# Scheme_UPS_RPI.net
KiCad netlist of a schematic drawn in Altium Designer
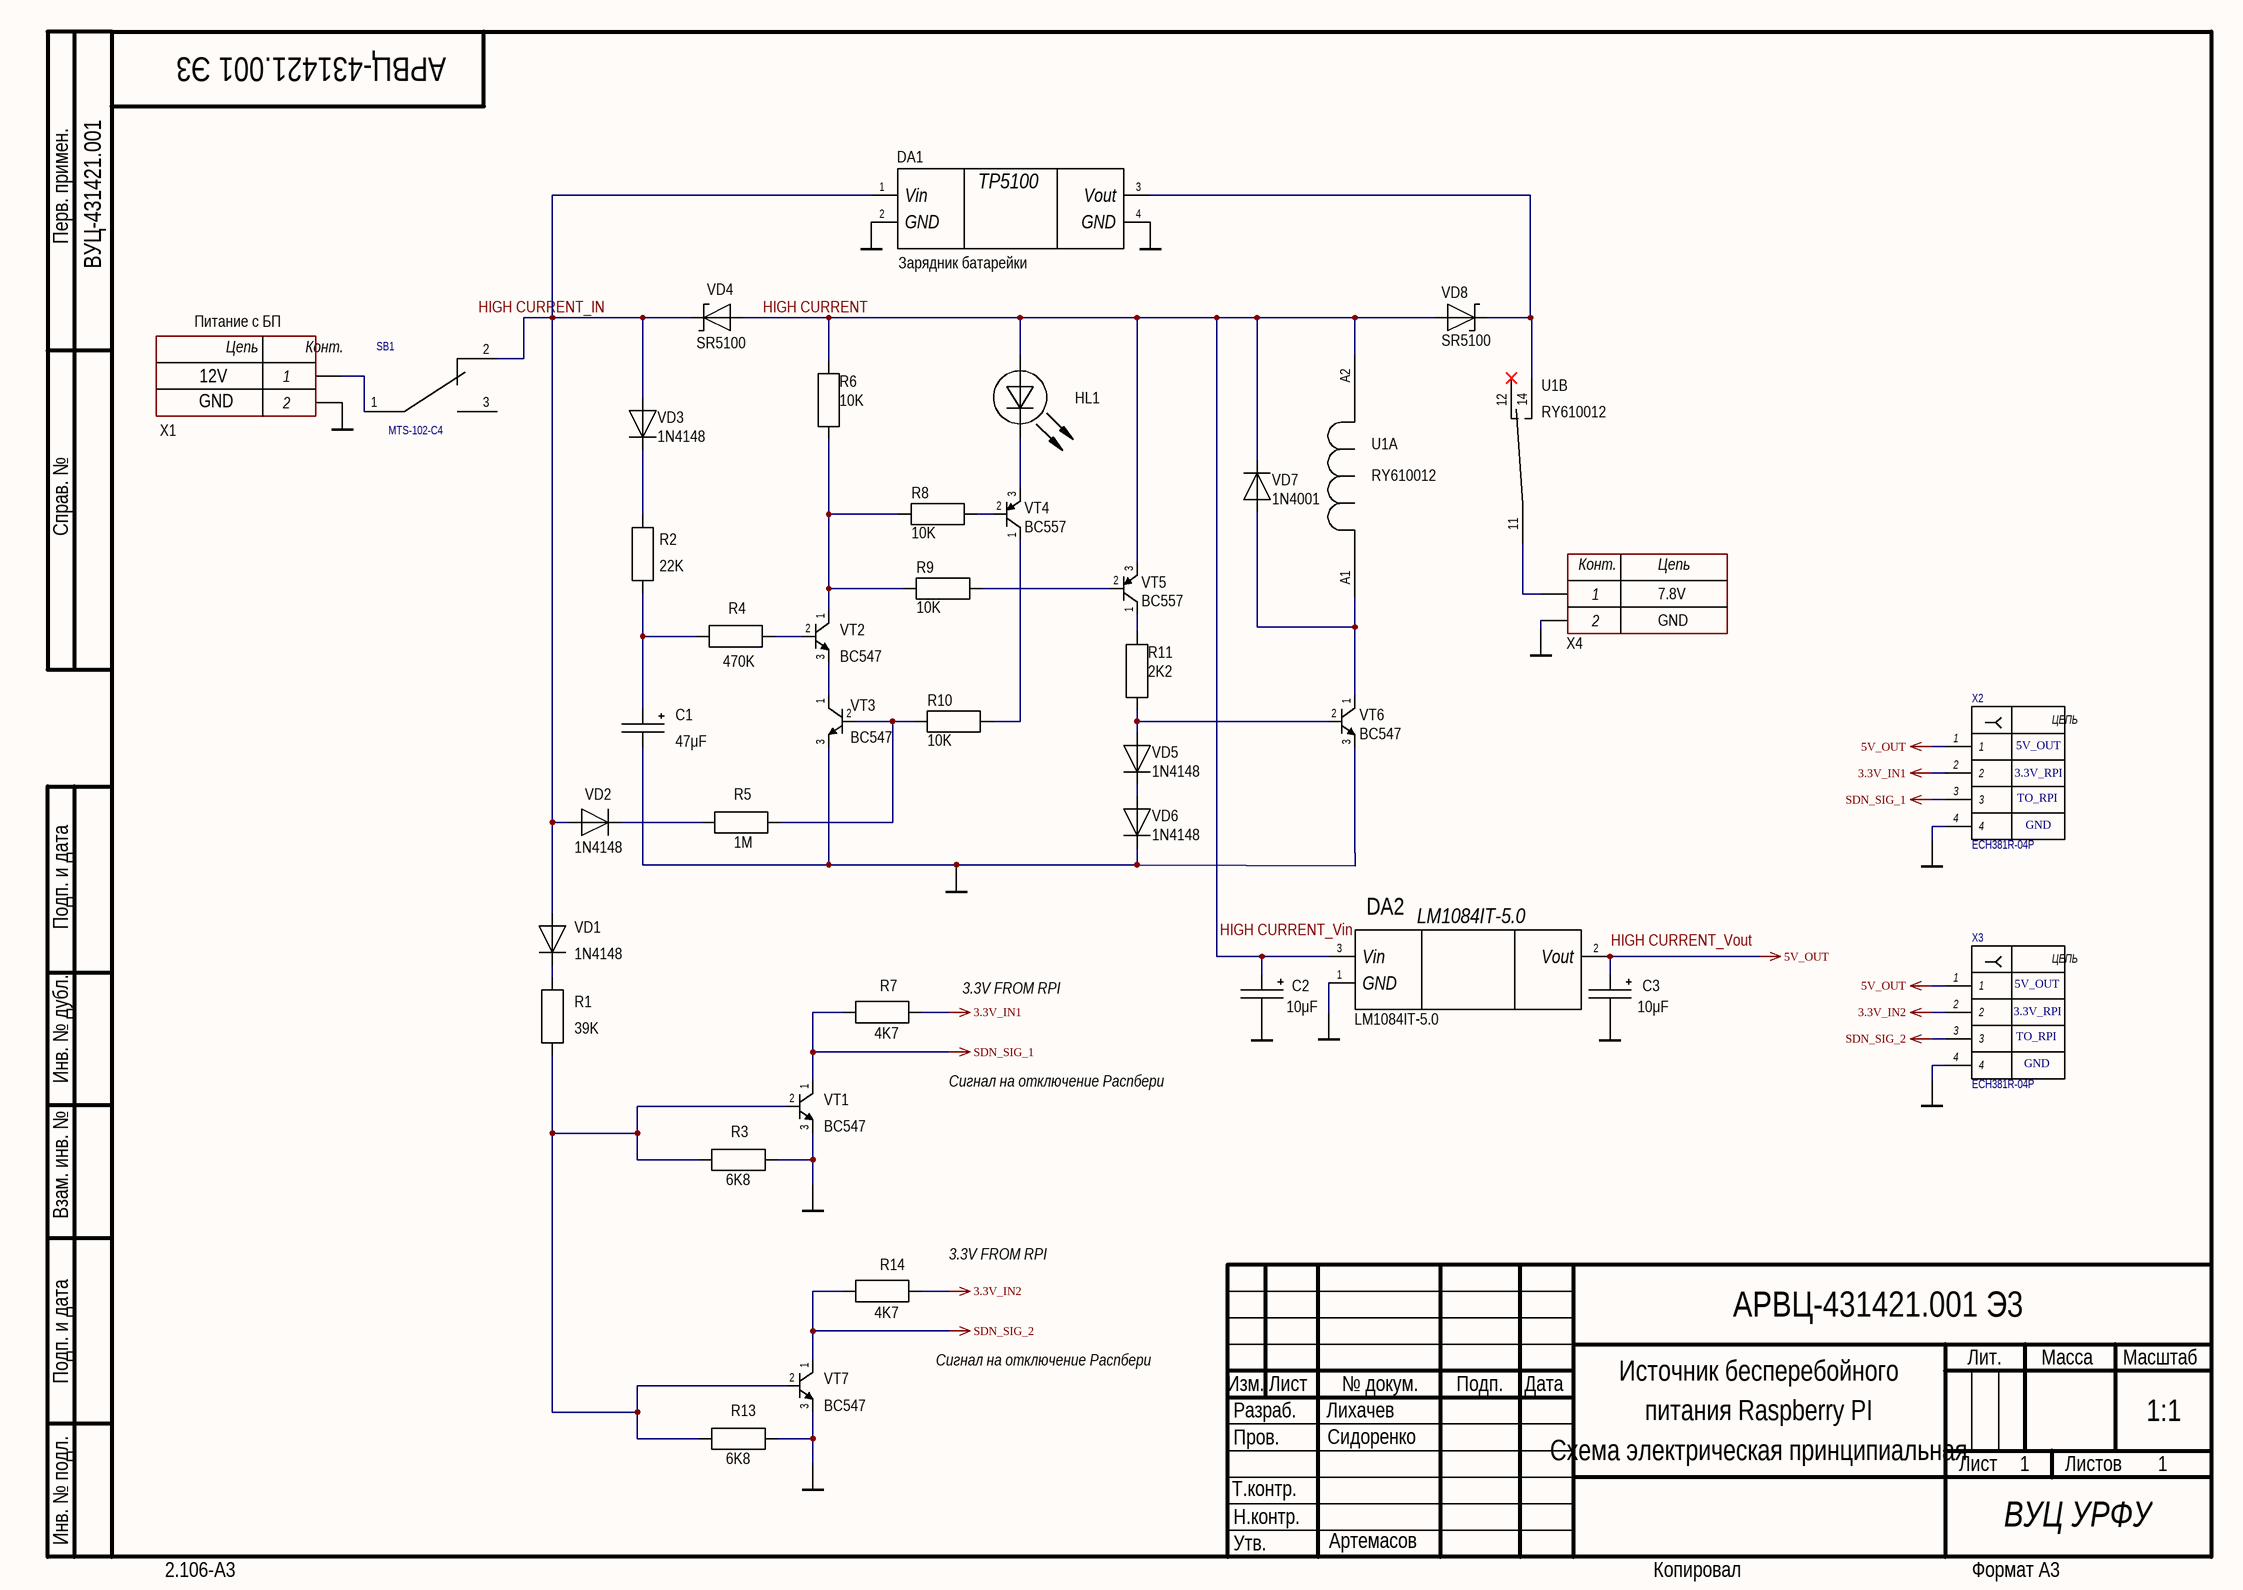
[diagram p0: Scheme_UPS_RPI.SchDoc]

(export (version "E")
  (design (tool "Eeschema 10.0.6"))
  (components
    (comp (ref "C1")
      (value "47μF")
      (footprint "CAP 5*11")
      (libsource (lib "UPS_sch_lib") (part "POLAR CAPACITOR"))
    )
    (comp (ref "C2") (value "10μF") (footprint "CAP 5*11") (libsource (lib "") (part "POLAR CAPACITOR_1")))
    (comp (ref "C3")
      (value "10μF")
      (footprint "CAP 5*11")
      (libsource (lib "UPS_sch_lib") (part "POLAR CAPACITOR"))
    )
    (comp (ref "DA1")
      (value "Зарядник батарейки")
      (footprint "Зарядник батарейки")
      (libsource (lib "UPS_sch_lib") (part "Зарядник батарейки"))
    )
    (comp (ref "DA2")
      (value "LM1084IT-5.0")
      (footprint "Под_провода_для_LM")
      (libsource (lib "UPS_sch_lib") (part "LM1084IT-5.0"))
    )
    (comp (ref "HL1") (value "~") (footprint "LED 1206") (libsource (lib "UPS_sch_lib") (part "LED_single")))
    (comp (ref "R1") (value "39K") (footprint "Резисторы") (libsource (lib "") (part "RESISTOR_1")))
    (comp (ref "R2") (value "22K") (footprint "Резисторы") (libsource (lib "") (part "RESISTOR_1")))
    (comp (ref "R3") (value "6K8") (footprint "RES: 1206") (libsource (lib "UPS_sch_lib") (part "RESISTOR")))
    (comp (ref "R4") (value "470K") (footprint "Резисторы") (libsource (lib "UPS_sch_lib") (part "RESISTOR")))
    (comp (ref "R5") (value "1M") (footprint "Резисторы") (libsource (lib "UPS_sch_lib") (part "RESISTOR")))
    (comp (ref "R6") (value "10K") (footprint "Резисторы") (libsource (lib "") (part "RESISTOR_1")))
    (comp (ref "R7") (value "4K7") (footprint "RES: 1206") (libsource (lib "UPS_sch_lib") (part "RESISTOR")))
    (comp (ref "R8") (value "10K") (footprint "Резисторы") (libsource (lib "UPS_sch_lib") (part "RESISTOR")))
    (comp (ref "R9") (value "10K") (footprint "Резисторы") (libsource (lib "UPS_sch_lib") (part "RESISTOR")))
    (comp (ref "R10") (value "10K") (footprint "Резисторы") (libsource (lib "UPS_sch_lib") (part "RESISTOR")))
    (comp (ref "R11") (value "2K2") (footprint "Резисторы") (libsource (lib "") (part "RESISTOR_1")))
    (comp (ref "R13") (value "6K8") (footprint "RES: 1206") (libsource (lib "UPS_sch_lib") (part "RESISTOR")))
    (comp (ref "R14") (value "4K7") (footprint "RES: 1206") (libsource (lib "UPS_sch_lib") (part "RESISTOR")))
    (comp (ref "SB1")
      (value "MTS-102-C4")
      (footprint "MTS-102-C4")
      (libsource (lib "UPS_sch_lib") (part "MTS-102-C4"))
    )
    (comp (ref "U1")
      (value "RY610012")
      (footprint "RELAY-SPDT_3.2mm")
      (description "No Description Available")
      (fields (field (name "COPYRIGHT") "Copyright (C) 2016 Accelerated Designs. All rights reserved"))
      (libsource (lib "UPS_sch_lib") (part "RY610012"))
    )
    (comp (ref "VD1")
      (value "~")
      (footprint "1N4148 DO-35")
      (fields (field (name "PARTNUMBER") "1N4148"))
      (libsource (lib "UPS_sch_lib") (part "1N4148"))
    )
    (comp (ref "VD2")
      (value "~")
      (footprint "1N4148 DO-35")
      (fields (field (name "PARTNUMBER") "1N4148"))
      (libsource (lib "UPS_sch_lib") (part "1N4148"))
    )
    (comp (ref "VD3")
      (value "~")
      (footprint "1N4148 DO-35")
      (fields (field (name "PARTNUMBER") "1N4148"))
      (libsource (lib "UPS_sch_lib") (part "1N4148"))
    )
    (comp (ref "VD4")
      (value "~")
      (footprint "Диод Шоттки SR5100")
      (fields (field (name "MANUFACTURER") "Diodes Incorporated") (field (name "PARTNUMBER") "SR5100"))
      (libsource (lib "UPS_sch_lib") (part "SR5100"))
    )
    (comp (ref "VD5")
      (value "~")
      (footprint "1N4148 DO-35")
      (fields (field (name "PARTNUMBER") "1N4148"))
      (libsource (lib "UPS_sch_lib") (part "1N4148"))
    )
    (comp (ref "VD6")
      (value "~")
      (footprint "1N4148 DO-35")
      (fields (field (name "PARTNUMBER") "1N4148"))
      (libsource (lib "UPS_sch_lib") (part "1N4148"))
    )
    (comp (ref "VD7")
      (value "~")
      (footprint "1N4001 DO-41")
      (fields
        (field (name "MANUFACTURER") "Micro Commercial")
        (field (name "VALUEMANUFACTURERPARTNUMBER") "Single diode, 75V, 150mA, 1V, 4ns, SOD-323, -55...+150°C")
        (field (name "VOLTAGE") "75V")
        (field (name "PARTNUMBER") "1N4001")
      )
      (libsource (lib "UPS_sch_lib") (part "1N4001"))
    )
    (comp (ref "VD8")
      (value "~")
      (footprint "Диод Шоттки SR5100")
      (fields (field (name "MANUFACTURER") "Diodes Incorporated") (field (name "PARTNUMBER") "SR5100"))
      (libsource (lib "UPS_sch_lib") (part "SR5100"))
    )
    (comp (ref "VT1")
      (value "~")
      (footprint "TO92")
      (fields
        (field (name "PARTNUMBER") "BC547")
        (field (name "MANUFACTURER") "ON Semiconductor")
        (field (name "VALUEMANUFACTURERPARTNUMBER") "NPN transistor, 45V, 100mA, 100MHz, 300mW, 0.6V, 420, SOT-23, -55...+125°C")
      )
      (libsource (lib "UPS_sch_lib") (part "BC547"))
    )
    (comp (ref "VT2")
      (value "~")
      (footprint "TO92")
      (fields
        (field (name "PARTNUMBER") "BC547")
        (field (name "MANUFACTURER") "ON Semiconductor")
        (field (name "VALUEMANUFACTURERPARTNUMBER") "NPN transistor, 45V, 100mA, 100MHz, 300mW, 0.6V, 420, SOT-23, -55...+125°C")
      )
      (libsource (lib "UPS_sch_lib") (part "BC547"))
    )
    (comp (ref "VT3")
      (value "~")
      (footprint "TO92")
      (fields
        (field (name "PARTNUMBER") "BC547")
        (field (name "MANUFACTURER") "ON Semiconductor")
        (field (name "VALUEMANUFACTURERPARTNUMBER") "NPN transistor, 45V, 100mA, 100MHz, 300mW, 0.6V, 420, SOT-23, -55...+125°C")
      )
      (libsource (lib "UPS_sch_lib") (part "BC547"))
    )
    (comp (ref "VT4")
      (value "~")
      (footprint "TO92")
      (fields
        (field (name "PARTNUMBER") "BC557")
        (field (name "MANUFACTURER") "ON Semiconductor")
        (field (name "VALUEMANUFACTURERPARTNUMBER") "PNP transistor, 45V, 100mA, 100MHz, 300mW, 0.65V, 220, SOT-23, -55...+125°C")
      )
      (libsource (lib "UPS_sch_lib") (part "BC557"))
    )
    (comp (ref "VT5")
      (value "~")
      (footprint "TO92")
      (fields
        (field (name "PARTNUMBER") "BC557")
        (field (name "MANUFACTURER") "ON Semiconductor")
        (field (name "VALUEMANUFACTURERPARTNUMBER") "PNP transistor, 45V, 100mA, 100MHz, 300mW, 0.65V, 220, SOT-23, -55...+125°C")
      )
      (libsource (lib "UPS_sch_lib") (part "BC557"))
    )
    (comp (ref "VT6")
      (value "~")
      (footprint "TO92")
      (fields
        (field (name "PARTNUMBER") "BC547")
        (field (name "MANUFACTURER") "ON Semiconductor")
        (field (name "VALUEMANUFACTURERPARTNUMBER") "NPN transistor, 45V, 100mA, 100MHz, 300mW, 0.6V, 420, SOT-23, -55...+125°C")
      )
      (libsource (lib "UPS_sch_lib") (part "BC547"))
    )
    (comp (ref "VT7")
      (value "~")
      (footprint "TO92")
      (fields
        (field (name "PARTNUMBER") "BC547")
        (field (name "MANUFACTURER") "ON Semiconductor")
        (field (name "VALUEMANUFACTURERPARTNUMBER") "NPN transistor, 45V, 100mA, 100MHz, 300mW, 0.6V, 420, SOT-23, -55...+125°C")
      )
      (libsource (lib "UPS_sch_lib") (part "BC547"))
    )
    (comp (ref "X1")
      (value "Питание с БП")
      (footprint "KLS2-EDV-5.08-02P-4")
      (libsource (lib "UPS_sch_lib") (part "CONNECTOR 2 PIN"))
    )
    (comp (ref "X2")
      (value "ECH381R-04P")
      (footprint "ECH381R-04P (KLS2-EDR-3.81-04P-4)")
      (description "4-pin R connector")
      (libsource (lib "UPS_sch_lib") (part "ECH381R-04P"))
    )
    (comp (ref "X3")
      (value "ECH381R-04P")
      (footprint "ECH381R-04P (KLS2-EDR-3.81-04P-4)")
      (description "4-pin R connector")
      (libsource (lib "UPS_sch_lib") (part "ECH381R-04P"))
    )
    (comp (ref "X4")
      (value "~")
      (footprint "KLS2-EDV-5.08-02P-4")
      (libsource (lib "UPS_sch_lib") (part "Держатель батарейки"))
    )
  )
  (nets
    (net (code "1") (name "/HIGH CURRENT") (class "Default")
      (node (ref "C2") (pin "1") (pinfunction "1_1") (pintype "passive"))
      (node (ref "DA2") (pin "3") (pinfunction "Vin_3") (pintype "passive"))
      (node (ref "HL1") (pin "1") (pinfunction "A_1") (pintype "passive"))
      (node (ref "R6") (pin "2") (pinfunction "2_2") (pintype "passive"))
      (node (ref "U1") (pin "A2") (pinfunction "A2_A2") (pintype "passive"))
      (node (ref "VD4") (pin "2") (pinfunction "2_2") (pintype "passive"))
      (node (ref "VD7") (pin "2") (pinfunction "2_2") (pintype "passive"))
      (node (ref "VD8") (pin "2") (pinfunction "2_2") (pintype "passive"))
      (node (ref "VT5") (pin "3") (pinfunction "E_3") (pintype "passive"))
    )
    (net (code "5") (name "3.3V_IN1") (class "Default")
      (node (ref "R7") (pin "2") (pinfunction "2_2") (pintype "passive"))
      (node (ref "X2") (pin "2") (pinfunction "2_2") (pintype "open_emitter"))
    )
    (net (code "6") (name "3.3V_IN2") (class "Default")
      (node (ref "R14") (pin "2") (pinfunction "2_2") (pintype "passive"))
      (node (ref "X3") (pin "2") (pinfunction "2_2") (pintype "open_emitter"))
    )
    (net (code "7") (name "5V_OUT") (class "Default")
      (node (ref "C3") (pin "1") (pinfunction "1_1") (pintype "passive"))
      (node (ref "DA2") (pin "2") (pinfunction "Vout_2") (pintype "passive"))
      (node (ref "X2") (pin "1") (pinfunction "1_1") (pintype "passive"))
      (node (ref "X3") (pin "1") (pinfunction "1_1") (pintype "passive"))
    )
    (net (code "8") (name "GND") (class "Default")
      (node (ref "C1") (pin "2") (pinfunction "2_2") (pintype "passive"))
      (node (ref "C2") (pin "2") (pinfunction "2_2") (pintype "passive"))
      (node (ref "C3") (pin "2") (pinfunction "2_2") (pintype "passive"))
      (node (ref "DA1") (pin "2") (pinfunction "GND_2") (pintype "passive"))
      (node (ref "DA1") (pin "4") (pinfunction "GND_4") (pintype "passive"))
      (node (ref "DA2") (pin "1") (pinfunction "GND_1") (pintype "passive"))
      (node (ref "R13") (pin "2") (pinfunction "2_2") (pintype "passive"))
      (node (ref "R3") (pin "2") (pinfunction "2_2") (pintype "passive"))
      (node (ref "VD6") (pin "2") (pinfunction "2_2") (pintype "passive"))
      (node (ref "VT1") (pin "3") (pinfunction "E_3") (pintype "passive"))
      (node (ref "VT3") (pin "3") (pinfunction "E_3") (pintype "passive"))
      (node (ref "VT6") (pin "3") (pinfunction "E_3") (pintype "passive"))
      (node (ref "VT7") (pin "3") (pinfunction "E_3") (pintype "passive"))
      (node (ref "X1") (pin "2") (pinfunction "2_2") (pintype "passive"))
      (node (ref "X2") (pin "4") (pinfunction "4_4") (pintype "open_emitter"))
      (node (ref "X3") (pin "4") (pinfunction "4_4") (pintype "open_emitter"))
      (node (ref "X4") (pin "2") (pinfunction "2_2") (pintype "passive"))
    )
    (net (code "9") (name "Net-(C1-Pad1)") (class "Default")
      (node (ref "C1") (pin "1") (pinfunction "1_1") (pintype "passive"))
      (node (ref "R2") (pin "1") (pinfunction "1_1") (pintype "passive"))
      (node (ref "R4") (pin "1") (pinfunction "1_1") (pintype "passive"))
    )
    (net (code "10") (name "Net-(DA1-Vin)") (class "Default")
      (node (ref "DA1") (pin "1") (pinfunction "Vin_1") (pintype "passive"))
      (node (ref "SB1") (pin "2") (pinfunction "2_2") (pintype "passive"))
      (node (ref "VD1") (pin "1") (pinfunction "1_1") (pintype "passive"))
      (node (ref "VD2") (pin "1") (pinfunction "1_1") (pintype "passive"))
      (node (ref "VD3") (pin "1") (pinfunction "1_1") (pintype "passive"))
      (node (ref "VD4") (pin "1") (pinfunction "1_1") (pintype "passive"))
    )
    (net (code "11") (name "Net-(DA1-Vout)") (class "Default")
      (node (ref "DA1") (pin "3") (pinfunction "Vout_3") (pintype "passive"))
      (node (ref "U1") (pin "14") (pinfunction "14_14") (pintype "passive"))
      (node (ref "VD8") (pin "1") (pinfunction "1_1") (pintype "passive"))
    )
    (net (code "12") (name "Net-(HL1-C)") (class "Default")
      (node (ref "HL1") (pin "2") (pinfunction "C_2") (pintype "passive"))
      (node (ref "VT4") (pin "3") (pinfunction "E_3") (pintype "passive"))
    )
    (net (code "13") (name "Net-(R1-Pad2)") (class "Default")
      (node (ref "R1") (pin "2") (pinfunction "2_2") (pintype "passive"))
      (node (ref "VD1") (pin "2") (pinfunction "2_2") (pintype "passive"))
    )
    (net (code "14") (name "Net-(R2-Pad2)") (class "Default")
      (node (ref "R2") (pin "2") (pinfunction "2_2") (pintype "passive"))
      (node (ref "VD3") (pin "2") (pinfunction "2_2") (pintype "passive"))
    )
    (net (code "15") (name "Net-(R5-Pad1)") (class "Default")
      (node (ref "R5") (pin "1") (pinfunction "1_1") (pintype "passive"))
      (node (ref "VD2") (pin "2") (pinfunction "2_2") (pintype "passive"))
    )
    (net (code "16") (name "Net-(SB1-Pad1)") (class "Default")
      (node (ref "SB1") (pin "1") (pinfunction "1_1") (pintype "passive"))
      (node (ref "X1") (pin "1") (pinfunction "1_1") (pintype "passive"))
    )
    (net (code "17") (name "Net-(U1-Pad11)") (class "Default")
      (node (ref "U1") (pin "11") (pinfunction "11_11") (pintype "passive"))
      (node (ref "X4") (pin "1") (pinfunction "1_1") (pintype "passive"))
    )
    (net (code "18") (name "Net-(VD5-Pad2)") (class "Default")
      (node (ref "VD5") (pin "2") (pinfunction "2_2") (pintype "passive"))
      (node (ref "VD6") (pin "1") (pinfunction "1_1") (pintype "passive"))
    )
    (net (code "19") (name "Net-(VT1-B)") (class "Default")
      (node (ref "R1") (pin "1") (pinfunction "1_1") (pintype "passive"))
      (node (ref "R13") (pin "1") (pinfunction "1_1") (pintype "passive"))
      (node (ref "R3") (pin "1") (pinfunction "1_1") (pintype "passive"))
      (node (ref "VT1") (pin "2") (pinfunction "B_2") (pintype "passive"))
      (node (ref "VT7") (pin "2") (pinfunction "B_2") (pintype "passive"))
    )
    (net (code "20") (name "Net-(VT2-B)") (class "Default")
      (node (ref "R4") (pin "2") (pinfunction "2_2") (pintype "passive"))
      (node (ref "VT2") (pin "2") (pinfunction "B_2") (pintype "passive"))
    )
    (net (code "21") (name "Net-(VT2-C)") (class "Default")
      (node (ref "R6") (pin "1") (pinfunction "1_1") (pintype "passive"))
      (node (ref "R8") (pin "1") (pinfunction "1_1") (pintype "passive"))
      (node (ref "R9") (pin "1") (pinfunction "1_1") (pintype "passive"))
      (node (ref "VT2") (pin "1") (pinfunction "C_1") (pintype "passive"))
    )
    (net (code "22") (name "Net-(VT2-E)") (class "Default")
      (node (ref "VT2") (pin "3") (pinfunction "E_3") (pintype "passive"))
      (node (ref "VT3") (pin "1") (pinfunction "C_1") (pintype "passive"))
    )
    (net (code "23") (name "Net-(VT3-B)") (class "Default")
      (node (ref "R10") (pin "1") (pinfunction "1_1") (pintype "passive"))
      (node (ref "R5") (pin "2") (pinfunction "2_2") (pintype "passive"))
      (node (ref "VT3") (pin "2") (pinfunction "B_2") (pintype "passive"))
    )
    (net (code "24") (name "Net-(VT4-B)") (class "Default")
      (node (ref "R8") (pin "2") (pinfunction "2_2") (pintype "passive"))
      (node (ref "VT4") (pin "2") (pinfunction "B_2") (pintype "passive"))
    )
    (net (code "25") (name "Net-(VT4-C)") (class "Default")
      (node (ref "R10") (pin "2") (pinfunction "2_2") (pintype "passive"))
      (node (ref "VT4") (pin "1") (pinfunction "C_1") (pintype "passive"))
    )
    (net (code "26") (name "Net-(VT5-B)") (class "Default")
      (node (ref "R9") (pin "2") (pinfunction "2_2") (pintype "passive"))
      (node (ref "VT5") (pin "2") (pinfunction "B_2") (pintype "passive"))
    )
    (net (code "27") (name "Net-(VT5-C)") (class "Default")
      (node (ref "R11") (pin "2") (pinfunction "2_2") (pintype "passive"))
      (node (ref "VT5") (pin "1") (pinfunction "C_1") (pintype "passive"))
    )
    (net (code "28") (name "Net-(VT6-B)") (class "Default")
      (node (ref "R11") (pin "1") (pinfunction "1_1") (pintype "passive"))
      (node (ref "VD5") (pin "1") (pinfunction "1_1") (pintype "passive"))
      (node (ref "VT6") (pin "2") (pinfunction "B_2") (pintype "passive"))
    )
    (net (code "29") (name "Net-(VT6-C)") (class "Default")
      (node (ref "U1") (pin "A1") (pinfunction "A1_A1") (pintype "passive"))
      (node (ref "VD7") (pin "1") (pinfunction "1_1") (pintype "passive"))
      (node (ref "VT6") (pin "1") (pinfunction "C_1") (pintype "passive"))
    )
    (net (code "30") (name "SDN_SIG_1") (class "Default")
      (node (ref "R7") (pin "1") (pinfunction "1_1") (pintype "passive"))
      (node (ref "VT1") (pin "1") (pinfunction "C_1") (pintype "passive"))
      (node (ref "X2") (pin "3") (pinfunction "3_3") (pintype "passive"))
    )
    (net (code "31") (name "SDN_SIG_2") (class "Default")
      (node (ref "R14") (pin "1") (pinfunction "1_1") (pintype "passive"))
      (node (ref "VT7") (pin "1") (pinfunction "C_1") (pintype "passive"))
      (node (ref "X3") (pin "3") (pinfunction "3_3") (pintype "passive"))
    )
    (net (code "32") (name "unconnected-(SB1-Pad3)") (class "Default")
      (node (ref "SB1") (pin "3") (pinfunction "3_3") (pintype "passive"))
    )
    (net (code "33") (name "unconnected-(U1-Pad12)") (class "Default")
      (node (ref "U1") (pin "12") (pinfunction "12_12") (pintype "passive+no_connect"))
    )
  )
)
